# bf2.net
KiCad netlist of a schematic drawn in EAGLE
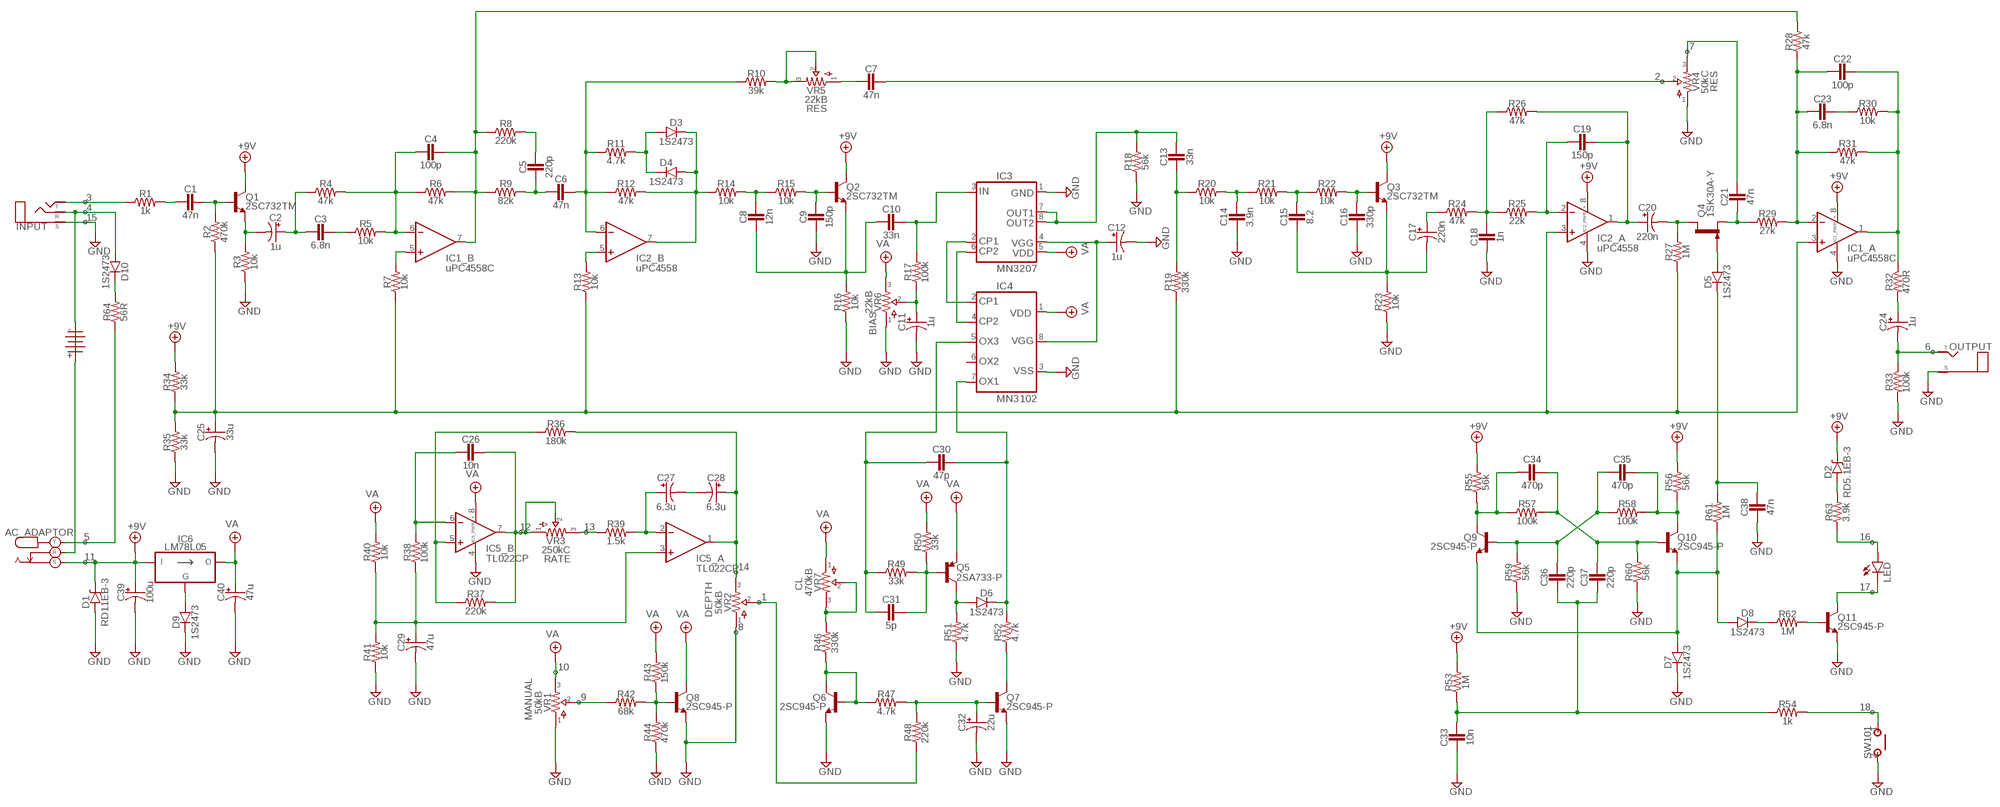
[diagram p0: schematic, sheet 1]

(export (version "E")
  (design (tool "Eeschema 10.0.6"))
  (components
    (comp (ref "1101")
      (value "BATTERY")
      (footprint "eagle-import:TWO_PADS")
      (libsource (lib "eagle-import") (part "BATTERY"))
    )
    (comp (ref "AC_ADAPTOR")
      (value "DC_KOBICONN")
      (footprint "eagle-import:DC_KOBICONN")
      (libsource (lib "eagle-import") (part "DC_KOBICONN"))
    )
    (comp (ref "C1")
      (value "47n")
      (footprint "eagle-import:BOX_SMALL")
      (libsource (lib "eagle-import") (part "CER/FILMBOX.1"))
    )
    (comp (ref "C2")
      (value "1u")
      (footprint "eagle-import:040_020")
      (libsource (lib "eagle-import") (part "0400"))
    )
    (comp (ref "C3")
      (value "6.8n")
      (footprint "eagle-import:BOX_SMALL")
      (libsource (lib "eagle-import") (part "CER/FILMBOX.1"))
    )
    (comp (ref "C4")
      (value "100p")
      (footprint "eagle-import:BOX_SMALL")
      (libsource (lib "eagle-import") (part "CER/FILMBOX.1"))
    )
    (comp (ref "C5")
      (value "220p")
      (footprint "eagle-import:BOX_SMALL")
      (libsource (lib "eagle-import") (part "CER/FILMBOX.1"))
    )
    (comp (ref "C6")
      (value "47n")
      (footprint "eagle-import:BOX_SMALL")
      (libsource (lib "eagle-import") (part "CER/FILMBOX.1"))
    )
    (comp (ref "C7")
      (value "47n")
      (footprint "eagle-import:BOX_SMALL")
      (libsource (lib "eagle-import") (part "CER/FILMBOX.1"))
    )
    (comp (ref "C8")
      (value "12n")
      (footprint "eagle-import:BOX_SMALL")
      (libsource (lib "eagle-import") (part "CER/FILMBOX.1"))
    )
    (comp (ref "C9")
      (value "150p")
      (footprint "eagle-import:BOX_SMALL")
      (libsource (lib "eagle-import") (part "CER/FILMBOX.1"))
    )
    (comp (ref "C10")
      (value "33n")
      (footprint "eagle-import:BOX_SMALL")
      (libsource (lib "eagle-import") (part "CER/FILMBOX.1"))
    )
    (comp (ref "C11")
      (value "1u")
      (footprint "eagle-import:040_020")
      (libsource (lib "eagle-import") (part "0400"))
    )
    (comp (ref "C12")
      (value "1u")
      (footprint "eagle-import:040_020")
      (libsource (lib "eagle-import") (part "0400"))
    )
    (comp (ref "C13")
      (value "33n")
      (footprint "eagle-import:BOX_SMALL")
      (libsource (lib "eagle-import") (part "CER/FILMBOX.1"))
    )
    (comp (ref "C14")
      (value "3.9n")
      (footprint "eagle-import:BOX_SMALL")
      (libsource (lib "eagle-import") (part "CER/FILMBOX.1"))
    )
    (comp (ref "C15")
      (value "8.2")
      (footprint "eagle-import:BOX_SMALL")
      (libsource (lib "eagle-import") (part "CER/FILMBOX.1"))
    )
    (comp (ref "C16")
      (value "330p")
      (footprint "eagle-import:BOX_SMALL")
      (libsource (lib "eagle-import") (part "CER/FILMBOX.1"))
    )
    (comp (ref "C17")
      (value "220n")
      (footprint "eagle-import:040_020")
      (libsource (lib "eagle-import") (part "0400"))
    )
    (comp (ref "C18")
      (value "1n")
      (footprint "eagle-import:BOX_SMALL")
      (libsource (lib "eagle-import") (part "CER/FILMBOX.1"))
    )
    (comp (ref "C19")
      (value "150p")
      (footprint "eagle-import:BOX_SMALL")
      (libsource (lib "eagle-import") (part "CER/FILMBOX.1"))
    )
    (comp (ref "C20")
      (value "220n")
      (footprint "eagle-import:040_020")
      (libsource (lib "eagle-import") (part "0400"))
    )
    (comp (ref "C21")
      (value "47n")
      (footprint "eagle-import:BOX_SMALL")
      (libsource (lib "eagle-import") (part "CER/FILMBOX.1"))
    )
    (comp (ref "C22")
      (value "100p")
      (footprint "eagle-import:BOX_SMALL")
      (libsource (lib "eagle-import") (part "CER/FILMBOX.1"))
    )
    (comp (ref "C23")
      (value "6.8n")
      (footprint "eagle-import:BOX_SMALL")
      (libsource (lib "eagle-import") (part "CER/FILMBOX.1"))
    )
    (comp (ref "C24")
      (value "1u")
      (footprint "eagle-import:040_020")
      (libsource (lib "eagle-import") (part "0400"))
    )
    (comp (ref "C25")
      (value "33u")
      (footprint "eagle-import:040_020")
      (libsource (lib "eagle-import") (part "0400"))
    )
    (comp (ref "C26")
      (value "10n")
      (footprint "eagle-import:BOX_SMALL")
      (libsource (lib "eagle-import") (part "CER/FILMBOX.1"))
    )
    (comp (ref "C27")
      (value "6.3u")
      (footprint "eagle-import:040_020")
      (libsource (lib "eagle-import") (part "0400"))
    )
    (comp (ref "C28")
      (value "6.3u")
      (footprint "eagle-import:040_020")
      (libsource (lib "eagle-import") (part "0400"))
    )
    (comp (ref "C29")
      (value "47u")
      (footprint "eagle-import:040_020")
      (libsource (lib "eagle-import") (part "0400"))
    )
    (comp (ref "C30")
      (value "47p")
      (footprint "eagle-import:BOX_SMALL")
      (libsource (lib "eagle-import") (part "CER/FILMBOX.1"))
    )
    (comp (ref "C31")
      (value "5p")
      (footprint "eagle-import:BOX_SMALL")
      (libsource (lib "eagle-import") (part "CER/FILMBOX.1"))
    )
    (comp (ref "C32")
      (value "22u")
      (footprint "eagle-import:040_020")
      (libsource (lib "eagle-import") (part "0400"))
    )
    (comp (ref "C33")
      (value "10n")
      (footprint "eagle-import:BOX_SMALL")
      (libsource (lib "eagle-import") (part "CER/FILMBOX.1"))
    )
    (comp (ref "C34")
      (value "470p")
      (footprint "eagle-import:BOX_SMALL")
      (libsource (lib "eagle-import") (part "CER/FILMBOX.1"))
    )
    (comp (ref "C35")
      (value "470p")
      (footprint "eagle-import:BOX_SMALL")
      (libsource (lib "eagle-import") (part "CER/FILMBOX.1"))
    )
    (comp (ref "C36")
      (value "220p")
      (footprint "eagle-import:BOX_SMALL")
      (libsource (lib "eagle-import") (part "CER/FILMBOX.1"))
    )
    (comp (ref "C37")
      (value "220p")
      (footprint "eagle-import:BOX_SMALL")
      (libsource (lib "eagle-import") (part "CER/FILMBOX.1"))
    )
    (comp (ref "C38")
      (value "47n")
      (footprint "eagle-import:BOX_SMALL")
      (libsource (lib "eagle-import") (part "CER/FILMBOX.1"))
    )
    (comp (ref "C39")
      (value "100u")
      (footprint "eagle-import:040_020")
      (libsource (lib "eagle-import") (part "0400"))
    )
    (comp (ref "C40")
      (value "47u")
      (footprint "eagle-import:040_020")
      (libsource (lib "eagle-import") (part "0400"))
    )
    (comp (ref "D1")
      (value "RD11EB-3")
      (footprint "eagle-import:DO41-2")
      (libsource (lib "eagle-import") (part "ZENER.2"))
    )
    (comp (ref "D2")
      (value "RD5.1EB-3")
      (footprint "eagle-import:DO41-2")
      (libsource (lib "eagle-import") (part "ZENER.2"))
    )
    (comp (ref "D3")
      (value "1S2473")
      (footprint "eagle-import:DO35-2")
      (libsource (lib "eagle-import") (part "DO35.2"))
    )
    (comp (ref "D4")
      (value "1S2473")
      (footprint "eagle-import:DO35-2")
      (libsource (lib "eagle-import") (part "DO35.2"))
    )
    (comp (ref "D5")
      (value "1S2473")
      (footprint "eagle-import:DO35-2")
      (libsource (lib "eagle-import") (part "DO35.2"))
    )
    (comp (ref "D6")
      (value "1S2473")
      (footprint "eagle-import:DO35-2")
      (libsource (lib "eagle-import") (part "DO35.2"))
    )
    (comp (ref "D7")
      (value "1S2473")
      (footprint "eagle-import:DO35-2")
      (libsource (lib "eagle-import") (part "DO35.2"))
    )
    (comp (ref "D8")
      (value "1S2473")
      (footprint "eagle-import:DO35-2")
      (libsource (lib "eagle-import") (part "DO35.2"))
    )
    (comp (ref "D9")
      (value "1S2473")
      (footprint "eagle-import:DO35-2")
      (libsource (lib "eagle-import") (part "DO35.2"))
    )
    (comp (ref "D10")
      (value "1S2473")
      (footprint "eagle-import:DO35-2")
      (libsource (lib "eagle-import") (part "DO35.2"))
    )
    (comp (ref "IC1")
      (value "uPC4558C")
      (footprint "eagle-import:DIL0")
      (libsource (lib "eagle-import") (part "DUALTH"))
    )
    (comp (ref "IC2")
      (value "uPC4558")
      (footprint "eagle-import:DIL0")
      (libsource (lib "eagle-import") (part "DUALTH"))
    )
    (comp (ref "IC3")
      (value "MN3207")
      (footprint "eagle-import:DIL0")
      (libsource (lib "eagle-import") (part "BL3208"))
    )
    (comp (ref "IC4")
      (value "MN3102")
      (footprint "eagle-import:DIL8")
      (libsource (lib "eagle-import") (part "CLOCK"))
    )
    (comp (ref "IC5")
      (value "TL022CP")
      (footprint "eagle-import:DIL0")
      (libsource (lib "eagle-import") (part "DUALTH"))
    )
    (comp (ref "IC6")
      (value "LM78L05")
      (footprint "eagle-import:TO92-")
      (libsource (lib "eagle-import") (part "LM78L05"))
    )
    (comp (ref "INPUT")
      (value "STEREO3PADS")
      (footprint "eagle-import:THREEPADS")
      (libsource (lib "eagle-import") (part "STEREO3PADS"))
    )
    (comp (ref "LED")
      (value "SLP1358")
      (footprint "eagle-import:3MM_D")
      (libsource (lib "eagle-import") (part "LED"))
    )
    (comp (ref "OUTPUT")
      (value "MONO")
      (footprint "eagle-import:TWO_PADS")
      (libsource (lib "eagle-import") (part "MONO"))
    )
    (comp (ref "Q1")
      (value "2SC732TM")
      (footprint "eagle-import:TO92-")
      (libsource (lib "eagle-import") (part "2SC828A"))
    )
    (comp (ref "Q2")
      (value "2SC732TM")
      (footprint "eagle-import:TO92-")
      (libsource (lib "eagle-import") (part "2SC828A"))
    )
    (comp (ref "Q3")
      (value "2SC732TM")
      (footprint "eagle-import:TO92-")
      (libsource (lib "eagle-import") (part "2SC828A"))
    )
    (comp (ref "Q4")
      (value "1SK30A-Y")
      (footprint "eagle-import:TO92-")
      (libsource (lib "eagle-import") (part "2N3819TO-92S"))
    )
    (comp (ref "Q5")
      (value "2SA733-P")
      (footprint "eagle-import:TO92-")
      (libsource (lib "eagle-import") (part "2N3906-"))
    )
    (comp (ref "Q6")
      (value "2SC945-P")
      (footprint "eagle-import:TO92-")
      (libsource (lib "eagle-import") (part "2SC828A"))
    )
    (comp (ref "Q7")
      (value "2SC945-P")
      (footprint "eagle-import:TO92-")
      (libsource (lib "eagle-import") (part "2SC828A"))
    )
    (comp (ref "Q8")
      (value "2SC945-P")
      (footprint "eagle-import:TO92-")
      (libsource (lib "eagle-import") (part "2SC828A"))
    )
    (comp (ref "Q9")
      (value "2SC945-P")
      (footprint "eagle-import:TO92-")
      (libsource (lib "eagle-import") (part "2SC828A"))
    )
    (comp (ref "Q10")
      (value "2SC945-P")
      (footprint "eagle-import:TO92-")
      (libsource (lib "eagle-import") (part "2SC828A"))
    )
    (comp (ref "Q11")
      (value "2SC945-P")
      (footprint "eagle-import:TO92-")
      (libsource (lib "eagle-import") (part "2SC828A"))
    )
    (comp (ref "R1")
      (value "1k")
      (footprint "eagle-import:R0207_3")
      (libsource (lib "eagle-import") (part "R_.3B"))
    )
    (comp (ref "R2")
      (value "470k")
      (footprint "eagle-import:R0207_3")
      (libsource (lib "eagle-import") (part "R_.3B"))
    )
    (comp (ref "R3")
      (value "10k")
      (footprint "eagle-import:R0207_3")
      (libsource (lib "eagle-import") (part "R_.3B"))
    )
    (comp (ref "R4")
      (value "47k")
      (footprint "eagle-import:R0207_3")
      (libsource (lib "eagle-import") (part "R_.3B"))
    )
    (comp (ref "R5")
      (value "10k")
      (footprint "eagle-import:R0207_3")
      (libsource (lib "eagle-import") (part "R_.3B"))
    )
    (comp (ref "R6")
      (value "47k")
      (footprint "eagle-import:R0207_3")
      (libsource (lib "eagle-import") (part "R_.3B"))
    )
    (comp (ref "R7")
      (value "10k")
      (footprint "eagle-import:R0207_3")
      (libsource (lib "eagle-import") (part "R_.3B"))
    )
    (comp (ref "R8")
      (value "220k")
      (footprint "eagle-import:R0207_3")
      (libsource (lib "eagle-import") (part "R_.3B"))
    )
    (comp (ref "R9")
      (value "82k")
      (footprint "eagle-import:R0207_3")
      (libsource (lib "eagle-import") (part "R_.3B"))
    )
    (comp (ref "R10")
      (value "39k")
      (footprint "eagle-import:R0207_3")
      (libsource (lib "eagle-import") (part "R_.3B"))
    )
    (comp (ref "R11")
      (value "4.7k")
      (footprint "eagle-import:R0207_3")
      (libsource (lib "eagle-import") (part "R_.3B"))
    )
    (comp (ref "R12")
      (value "47k")
      (footprint "eagle-import:R0207_3")
      (libsource (lib "eagle-import") (part "R_.3B"))
    )
    (comp (ref "R13")
      (value "10k")
      (footprint "eagle-import:R0207_3")
      (libsource (lib "eagle-import") (part "R_.3B"))
    )
    (comp (ref "R14")
      (value "10k")
      (footprint "eagle-import:R0207_3")
      (libsource (lib "eagle-import") (part "R_.3B"))
    )
    (comp (ref "R15")
      (value "10k")
      (footprint "eagle-import:R0207_3")
      (libsource (lib "eagle-import") (part "R_.3B"))
    )
    (comp (ref "R16")
      (value "10k")
      (footprint "eagle-import:R0207_3")
      (libsource (lib "eagle-import") (part "R_.3B"))
    )
    (comp (ref "R17")
      (value "100k")
      (footprint "eagle-import:R0207_3")
      (libsource (lib "eagle-import") (part "R_.3B"))
    )
    (comp (ref "R18")
      (value "56k")
      (footprint "eagle-import:R0207_3")
      (libsource (lib "eagle-import") (part "R_.3B"))
    )
    (comp (ref "R19")
      (value "330k")
      (footprint "eagle-import:R0207_3")
      (libsource (lib "eagle-import") (part "R_.3B"))
    )
    (comp (ref "R20")
      (value "10k")
      (footprint "eagle-import:R0207_3")
      (libsource (lib "eagle-import") (part "R_.3B"))
    )
    (comp (ref "R21")
      (value "10k")
      (footprint "eagle-import:R0207_3")
      (libsource (lib "eagle-import") (part "R_.3B"))
    )
    (comp (ref "R22")
      (value "10k")
      (footprint "eagle-import:R0207_3")
      (libsource (lib "eagle-import") (part "R_.3B"))
    )
    (comp (ref "R23")
      (value "10k")
      (footprint "eagle-import:R0207_3")
      (libsource (lib "eagle-import") (part "R_.3B"))
    )
    (comp (ref "R24")
      (value "47k")
      (footprint "eagle-import:R0207_3")
      (libsource (lib "eagle-import") (part "R_.3B"))
    )
    (comp (ref "R25")
      (value "22k")
      (footprint "eagle-import:R0207_3")
      (libsource (lib "eagle-import") (part "R_.3B"))
    )
    (comp (ref "R26")
      (value "47k")
      (footprint "eagle-import:R0207_3")
      (libsource (lib "eagle-import") (part "R_.3B"))
    )
    (comp (ref "R27")
      (value "1M")
      (footprint "eagle-import:R0207_3")
      (libsource (lib "eagle-import") (part "R_.3B"))
    )
    (comp (ref "R28")
      (value "47k")
      (footprint "eagle-import:R0207_3")
      (libsource (lib "eagle-import") (part "R_.3B"))
    )
    (comp (ref "R29")
      (value "27k")
      (footprint "eagle-import:R0207_3")
      (libsource (lib "eagle-import") (part "R_.3B"))
    )
    (comp (ref "R30")
      (value "10k")
      (footprint "eagle-import:R0207_3")
      (libsource (lib "eagle-import") (part "R_.3B"))
    )
    (comp (ref "R31")
      (value "47k")
      (footprint "eagle-import:R0207_3")
      (libsource (lib "eagle-import") (part "R_.3B"))
    )
    (comp (ref "R32")
      (value "470R")
      (footprint "eagle-import:R0207_3")
      (libsource (lib "eagle-import") (part "R_.3B"))
    )
    (comp (ref "R33")
      (value "100k")
      (footprint "eagle-import:R0207_3")
      (libsource (lib "eagle-import") (part "R_.3B"))
    )
    (comp (ref "R34")
      (value "33k")
      (footprint "eagle-import:R0207_3")
      (libsource (lib "eagle-import") (part "R_.3B"))
    )
    (comp (ref "R35")
      (value "33k")
      (footprint "eagle-import:R0207_3")
      (libsource (lib "eagle-import") (part "R_.3B"))
    )
    (comp (ref "R36")
      (value "180k")
      (footprint "eagle-import:R0207_3")
      (libsource (lib "eagle-import") (part "R_.3B"))
    )
    (comp (ref "R37")
      (value "220k")
      (footprint "eagle-import:R0207_3")
      (libsource (lib "eagle-import") (part "R_.3B"))
    )
    (comp (ref "R38")
      (value "100k")
      (footprint "eagle-import:R0207_3")
      (libsource (lib "eagle-import") (part "R_.3B"))
    )
    (comp (ref "R39")
      (value "1.5k")
      (footprint "eagle-import:R0207_3")
      (libsource (lib "eagle-import") (part "R_.3B"))
    )
    (comp (ref "R40")
      (value "10k")
      (footprint "eagle-import:R0207_3")
      (libsource (lib "eagle-import") (part "R_.3B"))
    )
    (comp (ref "R41")
      (value "10k")
      (footprint "eagle-import:R0207_3")
      (libsource (lib "eagle-import") (part "R_.3B"))
    )
    (comp (ref "R42")
      (value "68k")
      (footprint "eagle-import:R0207_3")
      (libsource (lib "eagle-import") (part "R_.3B"))
    )
    (comp (ref "R43")
      (value "150k")
      (footprint "eagle-import:R0207_3")
      (libsource (lib "eagle-import") (part "R_.3B"))
    )
    (comp (ref "R44")
      (value "470k")
      (footprint "eagle-import:R0207_3")
      (libsource (lib "eagle-import") (part "R_.3B"))
    )
    (comp (ref "R46")
      (value "330k")
      (footprint "eagle-import:R0207_3")
      (libsource (lib "eagle-import") (part "R_.3B"))
    )
    (comp (ref "R47")
      (value "4.7k")
      (footprint "eagle-import:R0207_3")
      (libsource (lib "eagle-import") (part "R_.3B"))
    )
    (comp (ref "R48")
      (value "220k")
      (footprint "eagle-import:R0207_3")
      (libsource (lib "eagle-import") (part "R_.3B"))
    )
    (comp (ref "R49")
      (value "33k")
      (footprint "eagle-import:R0207_3")
      (libsource (lib "eagle-import") (part "R_.3B"))
    )
    (comp (ref "R50")
      (value "33k")
      (footprint "eagle-import:R0207_3")
      (libsource (lib "eagle-import") (part "R_.3B"))
    )
    (comp (ref "R51")
      (value "4.7k")
      (footprint "eagle-import:R0207_3")
      (libsource (lib "eagle-import") (part "R_.3B"))
    )
    (comp (ref "R52")
      (value "4.7k")
      (footprint "eagle-import:R0207_3")
      (libsource (lib "eagle-import") (part "R_.3B"))
    )
    (comp (ref "R53")
      (value "1M")
      (footprint "eagle-import:R0207_3")
      (libsource (lib "eagle-import") (part "R_.3B"))
    )
    (comp (ref "R54")
      (value "1k")
      (footprint "eagle-import:R0207_3")
      (libsource (lib "eagle-import") (part "R_.3B"))
    )
    (comp (ref "R55")
      (value "56k")
      (footprint "eagle-import:R0207_3")
      (libsource (lib "eagle-import") (part "R_.3B"))
    )
    (comp (ref "R56")
      (value "56k")
      (footprint "eagle-import:R0207_3")
      (libsource (lib "eagle-import") (part "R_.3B"))
    )
    (comp (ref "R57")
      (value "100k")
      (footprint "eagle-import:R0207_3")
      (libsource (lib "eagle-import") (part "R_.3B"))
    )
    (comp (ref "R58")
      (value "100k")
      (footprint "eagle-import:R0207_3")
      (libsource (lib "eagle-import") (part "R_.3B"))
    )
    (comp (ref "R59")
      (value "56k")
      (footprint "eagle-import:R0207_3")
      (libsource (lib "eagle-import") (part "R_.3B"))
    )
    (comp (ref "R60")
      (value "56k")
      (footprint "eagle-import:R0207_3")
      (libsource (lib "eagle-import") (part "R_.3B"))
    )
    (comp (ref "R61")
      (value "1M")
      (footprint "eagle-import:R0207_3")
      (libsource (lib "eagle-import") (part "R_.3B"))
    )
    (comp (ref "R62")
      (value "1M")
      (footprint "eagle-import:R0207_3")
      (libsource (lib "eagle-import") (part "R_.3B"))
    )
    (comp (ref "R63")
      (value "3.9k")
      (footprint "eagle-import:R0207_3")
      (libsource (lib "eagle-import") (part "R_.3B"))
    )
    (comp (ref "R64")
      (value "56R")
      (footprint "eagle-import:R0207_3")
      (libsource (lib "eagle-import") (part "R_.3B"))
    )
    (comp (ref "SW101")
      (value "MOMENTARY")
      (footprint "eagle-import:SPST")
      (libsource (lib "eagle-import") (part "MOMENTARY"))
    )
    (comp (ref "VR1")
      (value "50kB")
      (footprint "eagle-import:16MM")
      (libsource (lib "eagle-import") (part "POTS16MM"))
    )
    (comp (ref "VR2")
      (value "50kB")
      (footprint "eagle-import:16MM")
      (libsource (lib "eagle-import") (part "POTS16MM"))
    )
    (comp (ref "VR3")
      (value "250kC")
      (footprint "eagle-import:16MM")
      (libsource (lib "eagle-import") (part "POTS16MM"))
    )
    (comp (ref "VR4")
      (value "50kC")
      (footprint "eagle-import:16MM")
      (libsource (lib "eagle-import") (part "POTS16MM"))
    )
    (comp (ref "VR5")
      (value "22kB")
      (footprint "eagle-import:16MM")
      (libsource (lib "eagle-import") (part "POTS16MM"))
    )
    (comp (ref "VR6")
      (value "22kB")
      (footprint "eagle-import:16MM")
      (libsource (lib "eagle-import") (part "POTS16MM"))
    )
    (comp (ref "VR7")
      (value "470kB")
      (footprint "eagle-import:16MM")
      (libsource (lib "eagle-import") (part "POTS16MM"))
    )
  )
  (nets
    (net (code "1") (name "+9V") (class "Default")
      (node (ref "AC_ADAPTOR") (pin "S") (pinfunction "S_S") (pintype "bidirectional"))
      (node (ref "C39") (pin "+") (pinfunction "+_+") (pintype "passive"))
      (node (ref "D1") (pin "C") (pinfunction "C_C") (pintype "passive"))
      (node (ref "D2") (pin "C") (pinfunction "C_C") (pintype "passive"))
      (node (ref "IC1") (pin "8") (pinfunction "V+_8") (pintype "power_in"))
      (node (ref "IC2") (pin "8") (pinfunction "V+_8") (pintype "power_in"))
      (node (ref "IC6") (pin "1") (pinfunction "VI_1") (pintype "input"))
      (node (ref "Q1") (pin "2") (pinfunction "C_2") (pintype "passive"))
      (node (ref "Q2") (pin "2") (pinfunction "C_2") (pintype "passive"))
      (node (ref "Q3") (pin "2") (pinfunction "C_2") (pintype "passive"))
      (node (ref "R34") (pin "2") (pinfunction "2_2") (pintype "passive"))
      (node (ref "R53") (pin "2") (pinfunction "2_2") (pintype "passive"))
      (node (ref "R55") (pin "2") (pinfunction "2_2") (pintype "passive"))
      (node (ref "R56") (pin "2") (pinfunction "2_2") (pintype "passive"))
    )
    (net (code "2") (name "GND") (class "Default")
      (node (ref "C11") (pin "-") (pinfunction "-_-") (pintype "passive"))
      (node (ref "C12") (pin "-") (pinfunction "-_-") (pintype "passive"))
      (node (ref "C14") (pin "2") (pinfunction "2_2") (pintype "passive"))
      (node (ref "C16") (pin "2") (pinfunction "2_2") (pintype "passive"))
      (node (ref "C18") (pin "2") (pinfunction "2_2") (pintype "passive"))
      (node (ref "C25") (pin "-") (pinfunction "-_-") (pintype "passive"))
      (node (ref "C29") (pin "-") (pinfunction "-_-") (pintype "passive"))
      (node (ref "C32") (pin "-") (pinfunction "-_-") (pintype "passive"))
      (node (ref "C33") (pin "2") (pinfunction "2_2") (pintype "passive"))
      (node (ref "C38") (pin "2") (pinfunction "2_2") (pintype "passive"))
      (node (ref "C39") (pin "-") (pinfunction "-_-") (pintype "passive"))
      (node (ref "C40") (pin "-") (pinfunction "-_-") (pintype "passive"))
      (node (ref "C9") (pin "2") (pinfunction "2_2") (pintype "passive"))
      (node (ref "D1") (pin "A") (pinfunction "A_A") (pintype "passive"))
      (node (ref "D7") (pin "C") (pinfunction "C_C") (pintype "passive"))
      (node (ref "D9") (pin "C") (pinfunction "C_C") (pintype "passive"))
      (node (ref "IC1") (pin "4") (pinfunction "V-_4") (pintype "power_in"))
      (node (ref "IC2") (pin "4") (pinfunction "V-_4") (pintype "power_in"))
      (node (ref "IC3") (pin "1") (pinfunction "1_1") (pintype "bidirectional"))
      (node (ref "IC4") (pin "3") (pinfunction "P$3_3") (pintype "bidirectional"))
      (node (ref "IC5") (pin "4") (pinfunction "V-_4") (pintype "power_in"))
      (node (ref "INPUT") (pin "SLEEVE") (pinfunction "S_SLEEVE") (pintype "passive"))
      (node (ref "OUTPUT") (pin "S") (pinfunction "SLEEVE_S") (pintype "passive"))
      (node (ref "Q11") (pin "3") (pinfunction "E_3") (pintype "passive"))
      (node (ref "Q6") (pin "3") (pinfunction "E_3") (pintype "passive"))
      (node (ref "Q7") (pin "3") (pinfunction "E_3") (pintype "passive"))
      (node (ref "Q8") (pin "3") (pinfunction "E_3") (pintype "passive"))
      (node (ref "R16") (pin "1") (pinfunction "1_1") (pintype "passive"))
      (node (ref "R18") (pin "1") (pinfunction "1_1") (pintype "passive"))
      (node (ref "R23") (pin "1") (pinfunction "1_1") (pintype "passive"))
      (node (ref "R3") (pin "1") (pinfunction "1_1") (pintype "passive"))
      (node (ref "R33") (pin "2") (pinfunction "2_2") (pintype "passive"))
      (node (ref "R35") (pin "1") (pinfunction "1_1") (pintype "passive"))
      (node (ref "R41") (pin "1") (pinfunction "1_1") (pintype "passive"))
      (node (ref "R44") (pin "1") (pinfunction "1_1") (pintype "passive"))
      (node (ref "R51") (pin "1") (pinfunction "1_1") (pintype "passive"))
      (node (ref "R59") (pin "1") (pinfunction "1_1") (pintype "passive"))
      (node (ref "R60") (pin "1") (pinfunction "1_1") (pintype "passive"))
      (node (ref "SW101") (pin "2") (pinfunction "S_2") (pintype "passive"))
      (node (ref "VR1") (pin "1") (pinfunction "1_1") (pintype "passive"))
      (node (ref "VR2") (pin "1") (pinfunction "1_1") (pintype "passive"))
      (node (ref "VR4") (pin "1") (pinfunction "1_1") (pintype "passive"))
      (node (ref "VR6") (pin "1") (pinfunction "1_1") (pintype "passive"))
    )
    (net (code "3") (name "Net-(1101-P$1)") (class "Default")
      (node (ref "1101") (pin "T") (pinfunction "P$1_T") (pintype "bidirectional"))
      (node (ref "AC_ADAPTOR") (pin "R") (pinfunction "R_R") (pintype "bidirectional"))
    )
    (net (code "4") (name "Net-(1101-P$2)") (class "Default")
      (node (ref "1101") (pin "S") (pinfunction "P$2_S") (pintype "bidirectional"))
      (node (ref "D10") (pin "A") (pinfunction "A_A") (pintype "passive"))
      (node (ref "INPUT") (pin "RING") (pinfunction "R_RING") (pintype "passive"))
    )
    (net (code "5") (name "Net-(AC_ADAPTOR-PadT)") (class "Default")
      (node (ref "AC_ADAPTOR") (pin "T") (pinfunction "T_T") (pintype "bidirectional"))
      (node (ref "R64") (pin "1") (pinfunction "1_1") (pintype "passive"))
    )
    (net (code "6") (name "Net-(C1-Pad2)") (class "Default")
      (node (ref "C1") (pin "2") (pinfunction "2_2") (pintype "passive"))
      (node (ref "R1") (pin "2") (pinfunction "2_2") (pintype "passive"))
    )
    (net (code "7") (name "Net-(C2-Pad+)") (class "Default")
      (node (ref "C2") (pin "+") (pinfunction "+_+") (pintype "passive"))
      (node (ref "C3") (pin "2") (pinfunction "2_2") (pintype "passive"))
      (node (ref "R4") (pin "1") (pinfunction "1_1") (pintype "passive"))
    )
    (net (code "8") (name "Net-(C3-Pad1)") (class "Default")
      (node (ref "C3") (pin "1") (pinfunction "1_1") (pintype "passive"))
      (node (ref "R5") (pin "1") (pinfunction "1_1") (pintype "passive"))
    )
    (net (code "9") (name "Net-(C5-Pad1)") (class "Default")
      (node (ref "C5") (pin "1") (pinfunction "1_1") (pintype "passive"))
      (node (ref "R8") (pin "2") (pinfunction "2_2") (pintype "passive"))
    )
    (net (code "10") (name "Net-(C5-Pad2)") (class "Default")
      (node (ref "C5") (pin "2") (pinfunction "2_2") (pintype "passive"))
      (node (ref "C6") (pin "2") (pinfunction "2_2") (pintype "passive"))
      (node (ref "R9") (pin "2") (pinfunction "2_2") (pintype "passive"))
    )
    (net (code "11") (name "Net-(C7-Pad1)") (class "Default")
      (node (ref "C7") (pin "1") (pinfunction "1_1") (pintype "passive"))
      (node (ref "VR4") (pin "2") (pinfunction "2_2") (pintype "passive"))
    )
    (net (code "12") (name "Net-(C7-Pad2)") (class "Default")
      (node (ref "C7") (pin "2") (pinfunction "2_2") (pintype "passive"))
      (node (ref "VR5") (pin "1") (pinfunction "1_1") (pintype "passive"))
    )
    (net (code "13") (name "Net-(C8-Pad1)") (class "Default")
      (node (ref "C8") (pin "1") (pinfunction "1_1") (pintype "passive"))
      (node (ref "R14") (pin "2") (pinfunction "2_2") (pintype "passive"))
      (node (ref "R15") (pin "1") (pinfunction "1_1") (pintype "passive"))
    )
    (net (code "14") (name "Net-(C10-Pad1)") (class "Default")
      (node (ref "C10") (pin "1") (pinfunction "1_1") (pintype "passive"))
      (node (ref "IC3") (pin "3") (pinfunction "3_3") (pintype "bidirectional"))
      (node (ref "R17") (pin "2") (pinfunction "2_2") (pintype "passive"))
    )
    (net (code "15") (name "Net-(C11-Pad+)") (class "Default")
      (node (ref "C11") (pin "+") (pinfunction "+_+") (pintype "passive"))
      (node (ref "R17") (pin "1") (pinfunction "1_1") (pintype "passive"))
      (node (ref "VR6") (pin "2") (pinfunction "2_2") (pintype "passive"))
    )
    (net (code "16") (name "Net-(C13-Pad1)") (class "Default")
      (node (ref "C13") (pin "1") (pinfunction "1_1") (pintype "passive"))
      (node (ref "IC3") (pin "7") (pinfunction "7_7") (pintype "bidirectional"))
      (node (ref "IC3") (pin "8") (pinfunction "8_8") (pintype "bidirectional"))
      (node (ref "R18") (pin "2") (pinfunction "2_2") (pintype "passive"))
    )
    (net (code "17") (name "Net-(C13-Pad2)") (class "Default")
      (node (ref "C13") (pin "2") (pinfunction "2_2") (pintype "passive"))
      (node (ref "R19") (pin "2") (pinfunction "2_2") (pintype "passive"))
      (node (ref "R20") (pin "1") (pinfunction "1_1") (pintype "passive"))
    )
    (net (code "18") (name "Net-(C14-Pad1)") (class "Default")
      (node (ref "C14") (pin "1") (pinfunction "1_1") (pintype "passive"))
      (node (ref "R20") (pin "2") (pinfunction "2_2") (pintype "passive"))
      (node (ref "R21") (pin "1") (pinfunction "1_1") (pintype "passive"))
    )
    (net (code "19") (name "Net-(C15-Pad1)") (class "Default")
      (node (ref "C15") (pin "1") (pinfunction "1_1") (pintype "passive"))
      (node (ref "R21") (pin "2") (pinfunction "2_2") (pintype "passive"))
      (node (ref "R22") (pin "1") (pinfunction "1_1") (pintype "passive"))
    )
    (net (code "20") (name "Net-(C17-Pad+)") (class "Default")
      (node (ref "C17") (pin "+") (pinfunction "+_+") (pintype "passive"))
      (node (ref "R24") (pin "1") (pinfunction "1_1") (pintype "passive"))
    )
    (net (code "21") (name "Net-(C18-Pad1)") (class "Default")
      (node (ref "C18") (pin "1") (pinfunction "1_1") (pintype "passive"))
      (node (ref "R24") (pin "2") (pinfunction "2_2") (pintype "passive"))
      (node (ref "R25") (pin "1") (pinfunction "1_1") (pintype "passive"))
      (node (ref "R26") (pin "1") (pinfunction "1_1") (pintype "passive"))
    )
    (net (code "22") (name "Net-(C21-Pad1)") (class "Default")
      (node (ref "C21") (pin "1") (pinfunction "1_1") (pintype "passive"))
      (node (ref "VR4") (pin "3") (pinfunction "3_3") (pintype "passive"))
    )
    (net (code "23") (name "Net-(C23-Pad1)") (class "Default")
      (node (ref "C23") (pin "1") (pinfunction "1_1") (pintype "passive"))
      (node (ref "R30") (pin "1") (pinfunction "1_1") (pintype "passive"))
    )
    (net (code "24") (name "Net-(C24-Pad+)") (class "Default")
      (node (ref "C24") (pin "+") (pinfunction "+_+") (pintype "passive"))
      (node (ref "R32") (pin "2") (pinfunction "2_2") (pintype "passive"))
    )
    (net (code "25") (name "Net-(C27-Pad-)") (class "Default")
      (node (ref "C27") (pin "-") (pinfunction "-_-") (pintype "passive"))
      (node (ref "C28") (pin "-") (pinfunction "-_-") (pintype "passive"))
    )
    (net (code "26") (name "Net-(C33-Pad1)") (class "Default")
      (node (ref "C33") (pin "1") (pinfunction "1_1") (pintype "passive"))
      (node (ref "C36") (pin "2") (pinfunction "2_2") (pintype "passive"))
      (node (ref "C37") (pin "2") (pinfunction "2_2") (pintype "passive"))
      (node (ref "R53") (pin "1") (pinfunction "1_1") (pintype "passive"))
      (node (ref "R54") (pin "1") (pinfunction "1_1") (pintype "passive"))
    )
    (net (code "27") (name "Net-(C38-Pad1)") (class "Default")
      (node (ref "C38") (pin "1") (pinfunction "1_1") (pintype "passive"))
      (node (ref "D5") (pin "C") (pinfunction "C_C") (pintype "passive"))
      (node (ref "R61") (pin "2") (pinfunction "2_2") (pintype "passive"))
    )
    (net (code "28") (name "Net-(D2-PadA)") (class "Default")
      (node (ref "D2") (pin "A") (pinfunction "A_A") (pintype "passive"))
      (node (ref "R63") (pin "2") (pinfunction "2_2") (pintype "passive"))
    )
    (net (code "29") (name "Net-(D3-PadA)") (class "Default")
      (node (ref "D3") (pin "A") (pinfunction "A_A") (pintype "passive"))
      (node (ref "D4") (pin "C") (pinfunction "C_C") (pintype "passive"))
      (node (ref "R11") (pin "2") (pinfunction "2_2") (pintype "passive"))
    )
    (net (code "30") (name "Net-(D8-PadC)") (class "Default")
      (node (ref "D8") (pin "C") (pinfunction "C_C") (pintype "passive"))
      (node (ref "R62") (pin "1") (pinfunction "1_1") (pintype "passive"))
    )
    (net (code "31") (name "Net-(D10-PadC)") (class "Default")
      (node (ref "D10") (pin "C") (pinfunction "C_C") (pintype "passive"))
      (node (ref "R64") (pin "2") (pinfunction "2_2") (pintype "passive"))
    )
    (net (code "32") (name "Net-(IC1A-+IN)") (class "Default")
      (node (ref "C25") (pin "+") (pinfunction "+_+") (pintype "passive"))
      (node (ref "IC1") (pin "3") (pinfunction "+IN_3") (pintype "input"))
      (node (ref "IC2") (pin "3") (pinfunction "+IN_3") (pintype "input"))
      (node (ref "R13") (pin "1") (pinfunction "1_1") (pintype "passive"))
      (node (ref "R19") (pin "1") (pinfunction "1_1") (pintype "passive"))
      (node (ref "R2") (pin "1") (pinfunction "1_1") (pintype "passive"))
      (node (ref "R27") (pin "1") (pinfunction "1_1") (pintype "passive"))
      (node (ref "R34") (pin "1") (pinfunction "1_1") (pintype "passive"))
      (node (ref "R35") (pin "2") (pinfunction "2_2") (pintype "passive"))
      (node (ref "R7") (pin "1") (pinfunction "1_1") (pintype "passive"))
    )
    (net (code "33") (name "Net-(IC1A--IN)") (class "Default")
      (node (ref "C22") (pin "2") (pinfunction "2_2") (pintype "passive"))
      (node (ref "C23") (pin "2") (pinfunction "2_2") (pintype "passive"))
      (node (ref "IC1") (pin "2") (pinfunction "-IN_2") (pintype "input"))
      (node (ref "R28") (pin "1") (pinfunction "1_1") (pintype "passive"))
      (node (ref "R29") (pin "2") (pinfunction "2_2") (pintype "passive"))
      (node (ref "R31") (pin "1") (pinfunction "1_1") (pintype "passive"))
    )
    (net (code "34") (name "Net-(IC1A-OUT)") (class "Default")
      (node (ref "C22") (pin "1") (pinfunction "1_1") (pintype "passive"))
      (node (ref "IC1") (pin "1") (pinfunction "OUT_1") (pintype "output"))
      (node (ref "R30") (pin "2") (pinfunction "2_2") (pintype "passive"))
      (node (ref "R31") (pin "2") (pinfunction "2_2") (pintype "passive"))
      (node (ref "R32") (pin "1") (pinfunction "1_1") (pintype "passive"))
    )
    (net (code "35") (name "Net-(IC1B-+IN)") (class "Default")
      (node (ref "IC1") (pin "5") (pinfunction "+IN_5") (pintype "input"))
      (node (ref "R7") (pin "2") (pinfunction "2_2") (pintype "passive"))
    )
    (net (code "36") (name "Net-(IC1B--IN)") (class "Default")
      (node (ref "C4") (pin "2") (pinfunction "2_2") (pintype "passive"))
      (node (ref "IC1") (pin "6") (pinfunction "-IN_6") (pintype "input"))
      (node (ref "R4") (pin "2") (pinfunction "2_2") (pintype "passive"))
      (node (ref "R5") (pin "2") (pinfunction "2_2") (pintype "passive"))
      (node (ref "R6") (pin "1") (pinfunction "1_1") (pintype "passive"))
    )
    (net (code "37") (name "Net-(IC1B-OUT)") (class "Default")
      (node (ref "C4") (pin "1") (pinfunction "1_1") (pintype "passive"))
      (node (ref "IC1") (pin "7") (pinfunction "OUT_7") (pintype "output"))
      (node (ref "R28") (pin "2") (pinfunction "2_2") (pintype "passive"))
      (node (ref "R6") (pin "2") (pinfunction "2_2") (pintype "passive"))
      (node (ref "R8") (pin "1") (pinfunction "1_1") (pintype "passive"))
      (node (ref "R9") (pin "1") (pinfunction "1_1") (pintype "passive"))
    )
    (net (code "38") (name "Net-(IC2A--IN)") (class "Default")
      (node (ref "C19") (pin "2") (pinfunction "2_2") (pintype "passive"))
      (node (ref "IC2") (pin "2") (pinfunction "-IN_2") (pintype "input"))
      (node (ref "R25") (pin "2") (pinfunction "2_2") (pintype "passive"))
    )
    (net (code "39") (name "Net-(IC2A-OUT)") (class "Default")
      (node (ref "C19") (pin "1") (pinfunction "1_1") (pintype "passive"))
      (node (ref "C20") (pin "+") (pinfunction "+_+") (pintype "passive"))
      (node (ref "IC2") (pin "1") (pinfunction "OUT_1") (pintype "output"))
      (node (ref "R26") (pin "2") (pinfunction "2_2") (pintype "passive"))
    )
    (net (code "40") (name "Net-(IC2B-+IN)") (class "Default")
      (node (ref "IC2") (pin "5") (pinfunction "+IN_5") (pintype "input"))
      (node (ref "R13") (pin "2") (pinfunction "2_2") (pintype "passive"))
    )
    (net (code "41") (name "Net-(IC2B--IN)") (class "Default")
      (node (ref "C6") (pin "1") (pinfunction "1_1") (pintype "passive"))
      (node (ref "IC2") (pin "6") (pinfunction "-IN_6") (pintype "input"))
      (node (ref "R10") (pin "1") (pinfunction "1_1") (pintype "passive"))
      (node (ref "R11") (pin "1") (pinfunction "1_1") (pintype "passive"))
      (node (ref "R12") (pin "1") (pinfunction "1_1") (pintype "passive"))
    )
    (net (code "42") (name "Net-(IC2B-OUT)") (class "Default")
      (node (ref "D3") (pin "C") (pinfunction "C_C") (pintype "passive"))
      (node (ref "D4") (pin "A") (pinfunction "A_A") (pintype "passive"))
      (node (ref "IC2") (pin "7") (pinfunction "OUT_7") (pintype "output"))
      (node (ref "R12") (pin "2") (pinfunction "2_2") (pintype "passive"))
      (node (ref "R14") (pin "1") (pinfunction "1_1") (pintype "passive"))
    )
    (net (code "43") (name "Net-(IC4-P$2)") (class "Default")
      (node (ref "IC3") (pin "2") (pinfunction "2_2") (pintype "bidirectional"))
      (node (ref "IC4") (pin "2") (pinfunction "P$2_2") (pintype "bidirectional"))
    )
    (net (code "44") (name "Net-(IC4-P$4)") (class "Default")
      (node (ref "IC3") (pin "6") (pinfunction "6_6") (pintype "bidirectional"))
      (node (ref "IC4") (pin "4") (pinfunction "P$4_4") (pintype "bidirectional"))
    )
    (net (code "45") (name "Net-(IC4-P$5)") (class "Default")
      (node (ref "C30") (pin "2") (pinfunction "2_2") (pintype "passive"))
      (node (ref "C31") (pin "2") (pinfunction "2_2") (pintype "passive"))
      (node (ref "IC4") (pin "5") (pinfunction "P$5_5") (pintype "bidirectional"))
      (node (ref "R49") (pin "1") (pinfunction "1_1") (pintype "passive"))
    )
    (net (code "46") (name "Net-(IC4-P$7)") (class "Default")
      (node (ref "C30") (pin "1") (pinfunction "1_1") (pintype "passive"))
      (node (ref "D6") (pin "C") (pinfunction "C_C") (pintype "passive"))
      (node (ref "IC4") (pin "7") (pinfunction "P$7_7") (pintype "bidirectional"))
      (node (ref "R52") (pin "2") (pinfunction "2_2") (pintype "passive"))
    )
    (net (code "47") (name "Net-(IC4-P$8)") (class "Default")
      (node (ref "C12") (pin "+") (pinfunction "+_+") (pintype "passive"))
      (node (ref "IC3") (pin "4") (pinfunction "4_4") (pintype "bidirectional"))
      (node (ref "IC4") (pin "8") (pinfunction "P$8_8") (pintype "bidirectional"))
    )
    (net (code "48") (name "Net-(IC5A-+IN)") (class "Default")
      (node (ref "C29") (pin "+") (pinfunction "+_+") (pintype "passive"))
      (node (ref "IC5") (pin "3") (pinfunction "+IN_3") (pintype "input"))
      (node (ref "R38") (pin "1") (pinfunction "1_1") (pintype "passive"))
      (node (ref "R40") (pin "1") (pinfunction "1_1") (pintype "passive"))
      (node (ref "R41") (pin "2") (pinfunction "2_2") (pintype "passive"))
    )
    (net (code "49") (name "Net-(IC5A--IN)") (class "Default")
      (node (ref "C27") (pin "+") (pinfunction "+_+") (pintype "passive"))
      (node (ref "IC5") (pin "2") (pinfunction "-IN_2") (pintype "input"))
      (node (ref "R39") (pin "2") (pinfunction "2_2") (pintype "passive"))
    )
    (net (code "50") (name "Net-(IC5A-OUT)") (class "Default")
      (node (ref "C28") (pin "+") (pinfunction "+_+") (pintype "passive"))
      (node (ref "IC5") (pin "1") (pinfunction "OUT_1") (pintype "output"))
      (node (ref "R36") (pin "2") (pinfunction "2_2") (pintype "passive"))
      (node (ref "VR2") (pin "3") (pinfunction "3_3") (pintype "passive"))
    )
    (net (code "51") (name "Net-(IC5B-+IN)") (class "Default")
      (node (ref "IC5") (pin "5") (pinfunction "+IN_5") (pintype "input"))
      (node (ref "R36") (pin "1") (pinfunction "1_1") (pintype "passive"))
      (node (ref "R37") (pin "1") (pinfunction "1_1") (pintype "passive"))
    )
    (net (code "52") (name "Net-(IC5B--IN)") (class "Default")
      (node (ref "C26") (pin "2") (pinfunction "2_2") (pintype "passive"))
      (node (ref "IC5") (pin "6") (pinfunction "-IN_6") (pintype "input"))
      (node (ref "R38") (pin "2") (pinfunction "2_2") (pintype "passive"))
    )
    (net (code "53") (name "Net-(IC5B-OUT)") (class "Default")
      (node (ref "C26") (pin "1") (pinfunction "1_1") (pintype "passive"))
      (node (ref "IC5") (pin "7") (pinfunction "OUT_7") (pintype "output"))
      (node (ref "R37") (pin "2") (pinfunction "2_2") (pintype "passive"))
      (node (ref "VR3") (pin "1") (pinfunction "1_1") (pintype "passive"))
      (node (ref "VR3") (pin "2") (pinfunction "2_2") (pintype "passive"))
    )
    (net (code "54") (name "Net-(IC6-GND)") (class "Default")
      (node (ref "D9") (pin "A") (pinfunction "A_A") (pintype "passive"))
      (node (ref "IC6") (pin "2") (pinfunction "GND_2") (pintype "passive"))
    )
    (net (code "55") (name "Net-(INPUT-T)") (class "Default")
      (node (ref "INPUT") (pin "TIP") (pinfunction "T_TIP") (pintype "passive"))
      (node (ref "R1") (pin "1") (pinfunction "1_1") (pintype "passive"))
    )
    (net (code "56") (name "Net-(LED-A)") (class "Default")
      (node (ref "LED") (pin "ANODE") (pinfunction "A_ANODE") (pintype "passive"))
      (node (ref "R63") (pin "1") (pinfunction "1_1") (pintype "passive"))
    )
    (net (code "57") (name "Net-(LED-C)") (class "Default")
      (node (ref "LED") (pin "P$1") (pinfunction "C_P$1") (pintype "passive"))
      (node (ref "Q11") (pin "2") (pinfunction "C_2") (pintype "passive"))
    )
    (net (code "58") (name "Net-(OUTPUT-TIP)") (class "Default")
      (node (ref "C24") (pin "-") (pinfunction "-_-") (pintype "passive"))
      (node (ref "OUTPUT") (pin "T") (pinfunction "TIP_T") (pintype "passive"))
      (node (ref "R33") (pin "1") (pinfunction "1_1") (pintype "passive"))
    )
    (net (code "59") (name "Net-(Q1-B)") (class "Default")
      (node (ref "C1") (pin "1") (pinfunction "1_1") (pintype "passive"))
      (node (ref "Q1") (pin "1") (pinfunction "B_1") (pintype "passive"))
      (node (ref "R2") (pin "2") (pinfunction "2_2") (pintype "passive"))
    )
    (net (code "60") (name "Net-(Q1-E)") (class "Default")
      (node (ref "C2") (pin "-") (pinfunction "-_-") (pintype "passive"))
      (node (ref "Q1") (pin "3") (pinfunction "E_3") (pintype "passive"))
      (node (ref "R3") (pin "2") (pinfunction "2_2") (pintype "passive"))
    )
    (net (code "61") (name "Net-(Q2-B)") (class "Default")
      (node (ref "C9") (pin "1") (pinfunction "1_1") (pintype "passive"))
      (node (ref "Q2") (pin "1") (pinfunction "B_1") (pintype "passive"))
      (node (ref "R15") (pin "2") (pinfunction "2_2") (pintype "passive"))
    )
    (net (code "62") (name "Net-(Q2-E)") (class "Default")
      (node (ref "C10") (pin "2") (pinfunction "2_2") (pintype "passive"))
      (node (ref "C8") (pin "2") (pinfunction "2_2") (pintype "passive"))
      (node (ref "Q2") (pin "3") (pinfunction "E_3") (pintype "passive"))
      (node (ref "R16") (pin "2") (pinfunction "2_2") (pintype "passive"))
    )
    (net (code "63") (name "Net-(Q3-B)") (class "Default")
      (node (ref "C16") (pin "1") (pinfunction "1_1") (pintype "passive"))
      (node (ref "Q3") (pin "1") (pinfunction "B_1") (pintype "passive"))
      (node (ref "R22") (pin "2") (pinfunction "2_2") (pintype "passive"))
    )
    (net (code "64") (name "Net-(Q3-E)") (class "Default")
      (node (ref "C15") (pin "2") (pinfunction "2_2") (pintype "passive"))
      (node (ref "C17") (pin "-") (pinfunction "-_-") (pintype "passive"))
      (node (ref "Q3") (pin "3") (pinfunction "E_3") (pintype "passive"))
      (node (ref "R23") (pin "2") (pinfunction "2_2") (pintype "passive"))
    )
    (net (code "65") (name "Net-(Q4-D)") (class "Default")
      (node (ref "C20") (pin "-") (pinfunction "-_-") (pintype "passive"))
      (node (ref "Q4") (pin "3") (pinfunction "D_3") (pintype "passive"))
      (node (ref "R27") (pin "2") (pinfunction "2_2") (pintype "passive"))
    )
    (net (code "66") (name "Net-(Q4-G)") (class "Default")
      (node (ref "D5") (pin "A") (pinfunction "A_A") (pintype "passive"))
      (node (ref "Q4") (pin "2") (pinfunction "G_2") (pintype "passive"))
    )
    (net (code "67") (name "Net-(Q4-S)") (class "Default")
      (node (ref "C21") (pin "2") (pinfunction "2_2") (pintype "passive"))
      (node (ref "Q4") (pin "1") (pinfunction "S_1") (pintype "passive"))
      (node (ref "R29") (pin "1") (pinfunction "1_1") (pintype "passive"))
    )
    (net (code "68") (name "Net-(Q5-B)") (class "Default")
      (node (ref "C31") (pin "1") (pinfunction "1_1") (pintype "passive"))
      (node (ref "Q5") (pin "2") (pinfunction "B_2") (pintype "passive"))
      (node (ref "R49") (pin "2") (pinfunction "2_2") (pintype "passive"))
      (node (ref "R50") (pin "1") (pinfunction "1_1") (pintype "passive"))
    )
    (net (code "69") (name "Net-(Q5-C)") (class "Default")
      (node (ref "D6") (pin "A") (pinfunction "A_A") (pintype "passive"))
      (node (ref "Q5") (pin "1") (pinfunction "C_1") (pintype "passive"))
      (node (ref "R51") (pin "2") (pinfunction "2_2") (pintype "passive"))
    )
    (net (code "70") (name "Net-(Q6-B)") (class "Default")
      (node (ref "Q6") (pin "1") (pinfunction "B_1") (pintype "passive"))
      (node (ref "Q6") (pin "2") (pinfunction "C_2") (pintype "passive"))
      (node (ref "R46") (pin "1") (pinfunction "1_1") (pintype "passive"))
      (node (ref "R47") (pin "1") (pinfunction "1_1") (pintype "passive"))
    )
    (net (code "71") (name "Net-(Q7-B)") (class "Default")
      (node (ref "C32") (pin "+") (pinfunction "+_+") (pintype "passive"))
      (node (ref "Q7") (pin "1") (pinfunction "B_1") (pintype "passive"))
      (node (ref "R47") (pin "2") (pinfunction "2_2") (pintype "passive"))
      (node (ref "R48") (pin "2") (pinfunction "2_2") (pintype "passive"))
    )
    (net (code "72") (name "Net-(Q7-C)") (class "Default")
      (node (ref "Q7") (pin "2") (pinfunction "C_2") (pintype "passive"))
      (node (ref "R52") (pin "1") (pinfunction "1_1") (pintype "passive"))
    )
    (net (code "73") (name "Net-(Q8-B)") (class "Default")
      (node (ref "Q8") (pin "1") (pinfunction "B_1") (pintype "passive"))
      (node (ref "R42") (pin "2") (pinfunction "2_2") (pintype "passive"))
      (node (ref "R43") (pin "1") (pinfunction "1_1") (pintype "passive"))
      (node (ref "R44") (pin "2") (pinfunction "2_2") (pintype "passive"))
    )
    (net (code "74") (name "Net-(Q9-B)") (class "Default")
      (node (ref "C35") (pin "2") (pinfunction "2_2") (pintype "passive"))
      (node (ref "C36") (pin "1") (pinfunction "1_1") (pintype "passive"))
      (node (ref "Q9") (pin "1") (pinfunction "B_1") (pintype "passive"))
      (node (ref "R58") (pin "1") (pinfunction "1_1") (pintype "passive"))
      (node (ref "R59") (pin "2") (pinfunction "2_2") (pintype "passive"))
    )
    (net (code "75") (name "Net-(Q9-C)") (class "Default")
      (node (ref "C34") (pin "2") (pinfunction "2_2") (pintype "passive"))
      (node (ref "Q9") (pin "2") (pinfunction "C_2") (pintype "passive"))
      (node (ref "R55") (pin "1") (pinfunction "1_1") (pintype "passive"))
      (node (ref "R57") (pin "1") (pinfunction "1_1") (pintype "passive"))
    )
    (net (code "76") (name "Net-(Q10-B)") (class "Default")
      (node (ref "C34") (pin "1") (pinfunction "1_1") (pintype "passive"))
      (node (ref "C37") (pin "1") (pinfunction "1_1") (pintype "passive"))
      (node (ref "Q10") (pin "1") (pinfunction "B_1") (pintype "passive"))
      (node (ref "R57") (pin "2") (pinfunction "2_2") (pintype "passive"))
      (node (ref "R60") (pin "2") (pinfunction "2_2") (pintype "passive"))
    )
    (net (code "77") (name "Net-(Q10-C)") (class "Default")
      (node (ref "C35") (pin "1") (pinfunction "1_1") (pintype "passive"))
      (node (ref "Q10") (pin "2") (pinfunction "C_2") (pintype "passive"))
      (node (ref "R56") (pin "1") (pinfunction "1_1") (pintype "passive"))
      (node (ref "R58") (pin "2") (pinfunction "2_2") (pintype "passive"))
    )
    (net (code "78") (name "Net-(Q10-E)") (class "Default")
      (node (ref "D7") (pin "A") (pinfunction "A_A") (pintype "passive"))
      (node (ref "D8") (pin "A") (pinfunction "A_A") (pintype "passive"))
      (node (ref "Q10") (pin "3") (pinfunction "E_3") (pintype "passive"))
      (node (ref "Q9") (pin "3") (pinfunction "E_3") (pintype "passive"))
      (node (ref "R61") (pin "1") (pinfunction "1_1") (pintype "passive"))
    )
    (net (code "79") (name "Net-(Q11-B)") (class "Default")
      (node (ref "Q11") (pin "1") (pinfunction "B_1") (pintype "passive"))
      (node (ref "R62") (pin "2") (pinfunction "2_2") (pintype "passive"))
    )
    (net (code "80") (name "Net-(R10-Pad2)") (class "Default")
      (node (ref "R10") (pin "2") (pinfunction "2_2") (pintype "passive"))
      (node (ref "VR5") (pin "2") (pinfunction "2_2") (pintype "passive"))
      (node (ref "VR5") (pin "3") (pinfunction "3_3") (pintype "passive"))
    )
    (net (code "81") (name "Net-(R39-Pad1)") (class "Default")
      (node (ref "R39") (pin "1") (pinfunction "1_1") (pintype "passive"))
      (node (ref "VR3") (pin "3") (pinfunction "3_3") (pintype "passive"))
    )
    (net (code "82") (name "Net-(R42-Pad1)") (class "Default")
      (node (ref "R42") (pin "1") (pinfunction "1_1") (pintype "passive"))
      (node (ref "VR1") (pin "2") (pinfunction "2_2") (pintype "passive"))
    )
    (net (code "83") (name "Net-(R46-Pad2)") (class "Default")
      (node (ref "R46") (pin "2") (pinfunction "2_2") (pintype "passive"))
      (node (ref "VR7") (pin "2") (pinfunction "2_2") (pintype "passive"))
      (node (ref "VR7") (pin "3") (pinfunction "3_3") (pintype "passive"))
    )
    (net (code "84") (name "Net-(R48-Pad1)") (class "Default")
      (node (ref "R48") (pin "1") (pinfunction "1_1") (pintype "passive"))
      (node (ref "VR2") (pin "2") (pinfunction "2_2") (pintype "passive"))
    )
    (net (code "85") (name "Net-(SW101-P)") (class "Default")
      (node (ref "R54") (pin "2") (pinfunction "2_2") (pintype "passive"))
      (node (ref "SW101") (pin "1") (pinfunction "P_1") (pintype "passive"))
    )
    (net (code "86") (name "VA") (class "Default")
      (node (ref "C40") (pin "+") (pinfunction "+_+") (pintype "passive"))
      (node (ref "IC3") (pin "5") (pinfunction "5_5") (pintype "bidirectional"))
      (node (ref "IC4") (pin "1") (pinfunction "P$1_1") (pintype "bidirectional"))
      (node (ref "IC5") (pin "8") (pinfunction "V+_8") (pintype "power_in"))
      (node (ref "IC6") (pin "3") (pinfunction "VO_3") (pintype "passive"))
      (node (ref "Q5") (pin "3") (pinfunction "E_3") (pintype "passive"))
      (node (ref "Q8") (pin "2") (pinfunction "C_2") (pintype "passive"))
      (node (ref "R40") (pin "2") (pinfunction "2_2") (pintype "passive"))
      (node (ref "R43") (pin "2") (pinfunction "2_2") (pintype "passive"))
      (node (ref "R50") (pin "2") (pinfunction "2_2") (pintype "passive"))
      (node (ref "VR1") (pin "3") (pinfunction "3_3") (pintype "passive"))
      (node (ref "VR6") (pin "3") (pinfunction "3_3") (pintype "passive"))
      (node (ref "VR7") (pin "1") (pinfunction "1_1") (pintype "passive"))
    )
    (net (code "87") (name "unconnected-(IC4-P$6-Pad6)") (class "Default")
      (node (ref "IC4") (pin "6") (pinfunction "P$6_6") (pintype "bidirectional"))
    )
  )
)
